# TELM0002ADC_BCR.net
KiCad netlist of a schematic drawn in Altium Designer
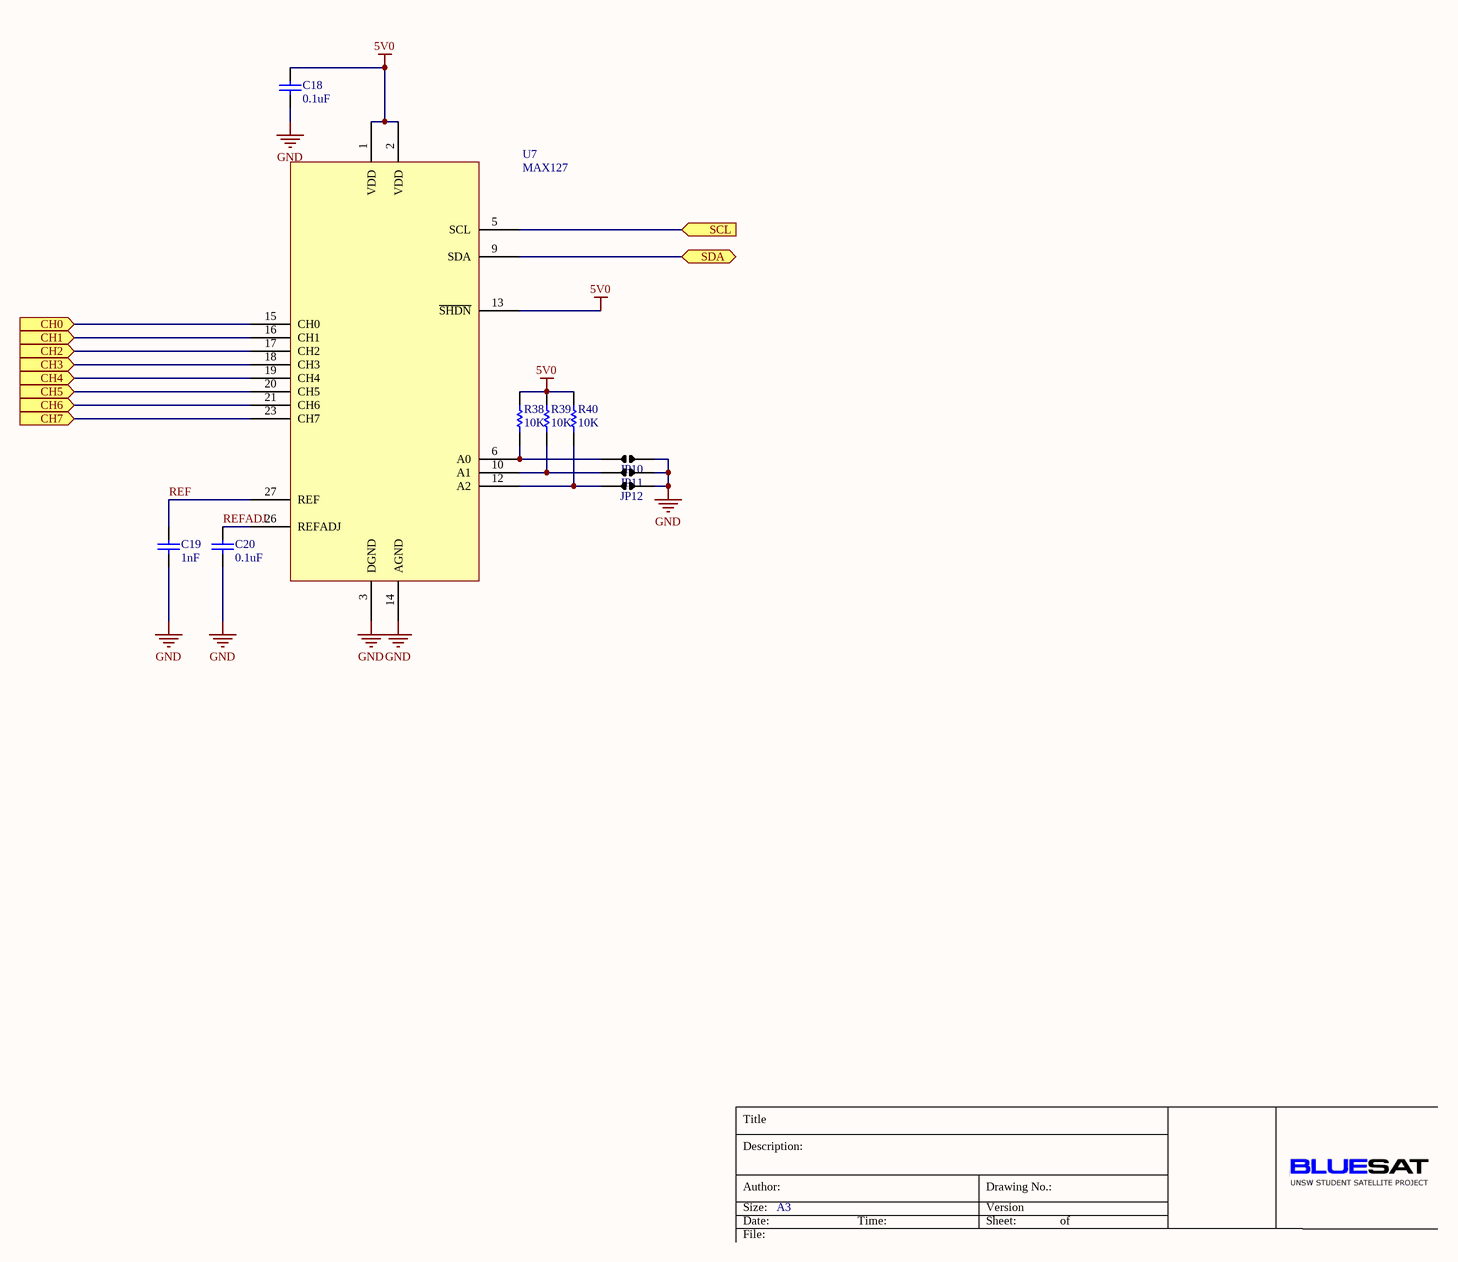
[diagram p0: TELM0002ADC_BCR.SchDoc]

(export (version "E")
  (design (tool "Eeschema 10.0.6"))
  (components
    (comp (ref "C18")
      (value "0.1uF")
      (footprint "CAPC2012M")
      (description "Capacitor")
      (fields (field (name "Comment") "Cap") (field (name "PUBLISHER") "Altium Limited"))
      (libsource (lib "Miscellaneous Devices") (part "Cap"))
    )
    (comp (ref "C19")
      (value "1nF")
      (footprint "CAPC2012M")
      (description "Capacitor")
      (fields (field (name "Comment") "Cap") (field (name "PUBLISHER") "Altium Limited"))
      (libsource (lib "Miscellaneous Devices") (part "Cap"))
    )
    (comp (ref "C20")
      (value "0.1uF")
      (footprint "CAPC2012M")
      (description "Capacitor")
      (fields (field (name "Comment") "Cap") (field (name "PUBLISHER") "Altium Limited"))
      (libsource (lib "Miscellaneous Devices") (part "Cap"))
    )
    (comp (ref "JP10")
      (value "Jumper")
      (footprint "Solder Jumper C")
      (description "Solder Bridge")
      (libsource (lib "Schlib1") (part "Solder Bridge"))
    )
    (comp (ref "JP11")
      (value "Jumper")
      (footprint "Solder Jumper C")
      (description "Solder Bridge")
      (libsource (lib "Schlib1") (part "Solder Bridge"))
    )
    (comp (ref "JP12")
      (value "Jumper")
      (footprint "Solder Jumper C")
      (description "Solder Bridge")
      (libsource (lib "Schlib1") (part "Solder Bridge"))
    )
    (comp (ref "R38")
      (value "10K")
      (footprint "RESC2012M")
      (description "Resistor")
      (fields (field (name "Comment") "0805 Resistor") (field (name "PUBLISHER") "Altium Limited"))
      (libsource (lib "Miscellaneous Devices") (part "Res1"))
    )
    (comp (ref "R39")
      (value "10K")
      (footprint "RESC2012M")
      (description "Resistor")
      (fields (field (name "Comment") "0805 Resistor") (field (name "PUBLISHER") "Altium Limited"))
      (libsource (lib "Miscellaneous Devices") (part "Res1"))
    )
    (comp (ref "R40")
      (value "10K")
      (footprint "RESC2012M")
      (description "Resistor")
      (fields (field (name "Comment") "0805 Resistor") (field (name "PUBLISHER") "Altium Limited"))
      (libsource (lib "Miscellaneous Devices") (part "Res1"))
    )
    (comp (ref "U7")
      (value "MAX127")
      (footprint "SSOP28 - MAX127")
      (description "8 Channel, 12 bit, I2C DAS")
      (libsource (lib "Schlib1") (part "MAX127"))
    )
  )
  (nets
    (net (code "1") (name "/CH0") (class "Default")
      (node (ref "U7") (pin "15") (pinfunction "CH0_15") (pintype "passive"))
    )
    (net (code "2") (name "/CH1") (class "Default")
      (node (ref "U7") (pin "16") (pinfunction "CH1_16") (pintype "passive"))
    )
    (net (code "3") (name "/CH2") (class "Default")
      (node (ref "U7") (pin "17") (pinfunction "CH2_17") (pintype "passive"))
    )
    (net (code "4") (name "/CH3") (class "Default")
      (node (ref "U7") (pin "18") (pinfunction "CH3_18") (pintype "passive"))
    )
    (net (code "5") (name "/CH4") (class "Default")
      (node (ref "U7") (pin "19") (pinfunction "CH4_19") (pintype "passive"))
    )
    (net (code "6") (name "/CH5") (class "Default")
      (node (ref "U7") (pin "20") (pinfunction "CH5_20") (pintype "passive"))
    )
    (net (code "7") (name "/CH6") (class "Default")
      (node (ref "U7") (pin "21") (pinfunction "CH6_21") (pintype "passive"))
    )
    (net (code "8") (name "/CH7") (class "Default")
      (node (ref "U7") (pin "23") (pinfunction "CH7_23") (pintype "passive"))
    )
    (net (code "9") (name "/REF") (class "Default")
      (node (ref "C19") (pin "1") (pinfunction "1_1") (pintype "passive"))
      (node (ref "U7") (pin "27") (pinfunction "REF_27") (pintype "passive"))
    )
    (net (code "10") (name "/REFADJ") (class "Default")
      (node (ref "C20") (pin "1") (pinfunction "1_1") (pintype "passive"))
      (node (ref "U7") (pin "26") (pinfunction "REFADJ_26") (pintype "passive"))
    )
    (net (code "11") (name "/SCL") (class "Default")
      (node (ref "U7") (pin "5") (pinfunction "SCL_5") (pintype "passive"))
    )
    (net (code "12") (name "/SDA") (class "Default")
      (node (ref "U7") (pin "9") (pinfunction "SDA_9") (pintype "passive"))
    )
    (net (code "13") (name "5V0") (class "Default")
      (node (ref "C18") (pin "1") (pinfunction "1_1") (pintype "passive"))
      (node (ref "R38") (pin "1") (pinfunction "1_1") (pintype "passive"))
      (node (ref "R39") (pin "1") (pinfunction "1_1") (pintype "passive"))
      (node (ref "R40") (pin "1") (pinfunction "1_1") (pintype "passive"))
      (node (ref "U7") (pin "1") (pinfunction "VDD_1") (pintype "passive"))
      (node (ref "U7") (pin "13") (pinfunction "~{SHDN}_13") (pintype "passive"))
      (node (ref "U7") (pin "2") (pinfunction "VDD_2") (pintype "passive"))
    )
    (net (code "14") (name "GND") (class "Default")
      (node (ref "C18") (pin "2") (pinfunction "2_2") (pintype "passive"))
      (node (ref "C19") (pin "2") (pinfunction "2_2") (pintype "passive"))
      (node (ref "C20") (pin "2") (pinfunction "2_2") (pintype "passive"))
      (node (ref "JP10") (pin "2") (pinfunction "2_2") (pintype "passive"))
      (node (ref "JP11") (pin "2") (pinfunction "2_2") (pintype "passive"))
      (node (ref "JP12") (pin "2") (pinfunction "2_2") (pintype "passive"))
      (node (ref "U7") (pin "14") (pinfunction "AGND_14") (pintype "passive"))
      (node (ref "U7") (pin "3") (pinfunction "DGND_3") (pintype "passive"))
    )
    (net (code "15") (name "Net-(U7-A0)") (class "Default")
      (node (ref "JP10") (pin "1") (pinfunction "1_1") (pintype "passive"))
      (node (ref "R38") (pin "2") (pinfunction "2_2") (pintype "passive"))
      (node (ref "U7") (pin "6") (pinfunction "A0_6") (pintype "passive"))
    )
    (net (code "16") (name "Net-(U7-A1)") (class "Default")
      (node (ref "JP11") (pin "1") (pinfunction "1_1") (pintype "passive"))
      (node (ref "R39") (pin "2") (pinfunction "2_2") (pintype "passive"))
      (node (ref "U7") (pin "10") (pinfunction "A1_10") (pintype "passive"))
    )
    (net (code "17") (name "Net-(U7-A2)") (class "Default")
      (node (ref "JP12") (pin "1") (pinfunction "1_1") (pintype "passive"))
      (node (ref "R40") (pin "2") (pinfunction "2_2") (pintype "passive"))
      (node (ref "U7") (pin "12") (pinfunction "A2_12") (pintype "passive"))
    )
  )
)
